# GPS.net
KiCad netlist of a schematic drawn in Altium Designer
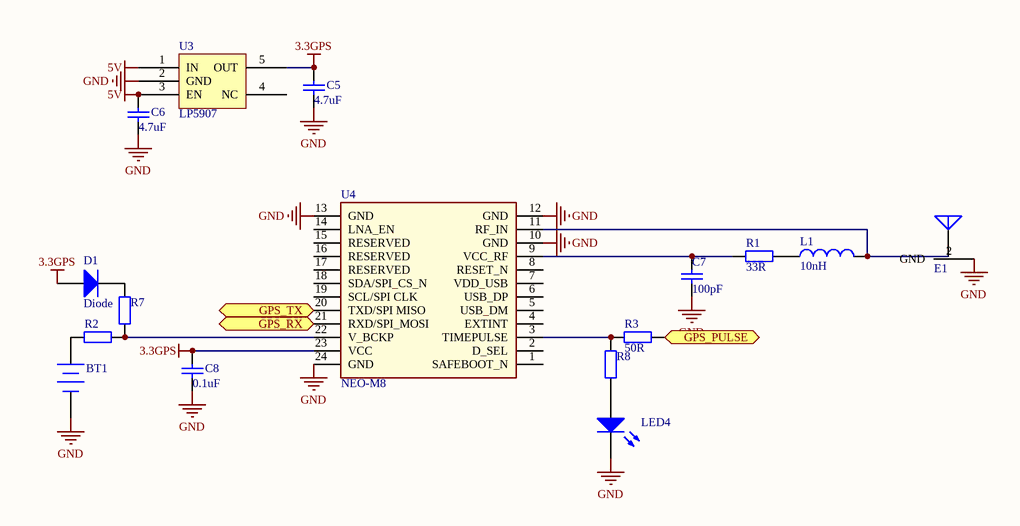
[diagram p0: GPS.SchDoc]

(export (version "E")
  (design (tool "Eeschema 10.0.6"))
  (components
    (comp (ref "BT1")
      (value "Battery")
      (footprint "XH414H-IV01E")
      (description "Multicell Battery")
      (fields (field (name "PUBLISHER") "Altium Limited"))
      (libsource (lib "Miscellaneous Devices") (part "Battery"))
    )
    (comp (ref "C5")
      (value "4.7uF")
      (footprint "0603")
      (description "Capacitor")
      (fields (field (name "PUBLISHER") "Altium Limited"))
      (libsource (lib "RTC6705") (part "Cap"))
    )
    (comp (ref "C6")
      (value "4.7uF")
      (footprint "0603")
      (description "Capacitor")
      (fields (field (name "PUBLISHER") "Altium Limited"))
      (libsource (lib "RTC6705") (part "Cap"))
    )
    (comp (ref "C7")
      (value "100pF")
      (footprint "0402")
      (description "Capacitor")
      (fields (field (name "PUBLISHER") "Altium Limited"))
      (libsource (lib "RTC6705") (part "Cap"))
    )
    (comp (ref "C8")
      (value "0.1uF")
      (footprint "0402")
      (description "Capacitor")
      (fields (field (name "PUBLISHER") "Altium Limited"))
      (libsource (lib "RTC6705") (part "Cap"))
    )
    (comp (ref "D1")
      (value "Diode")
      (footprint "LC-SOD-323")
      (description "Default Diode")
      (fields (field (name "PUBLISHER") "Altium Limited"))
      (libsource (lib "Miscellaneous Devices") (part "Diode"))
    )
    (comp (ref "E1")
      (value "Antenna")
      (footprint "IPEX")
      (description "Generic Antenna")
      (fields (field (name "PUBLISHER") "Altium Limited"))
      (libsource (lib "Miscellaneous Devices") (part "Antenna"))
    )
    (comp (ref "L1")
      (value "10nH")
      (footprint "0402")
      (description "Inductor")
      (fields (field (name "PUBLISHER") "Altium Limited"))
      (libsource (lib "Miscellaneous Devices") (part "Inductor"))
    )
    (comp (ref "LED4")
      (value "LED0")
      (footprint "0603")
      (description "Typical INFRARED GaAs LED")
      (fields (field (name "PUBLISHER") "Altium Limited"))
      (libsource (lib "Miscellaneous Devices") (part "LED0"))
    )
    (comp (ref "R1")
      (value "33R")
      (footprint "0402")
      (description "Resistor")
      (fields (field (name "PUBLISHER") "Altium Limited"))
      (libsource (lib "Miscellaneous Devices") (part "Res2"))
    )
    (comp (ref "R2")
      (value "~")
      (footprint "0402")
      (description "Resistor")
      (fields (field (name "PUBLISHER") "Altium Limited"))
      (libsource (lib "Miscellaneous Devices") (part "Res2"))
    )
    (comp (ref "R3")
      (value "50R")
      (footprint "0402")
      (description "Resistor")
      (fields (field (name "PUBLISHER") "Altium Limited"))
      (libsource (lib "RTC6705") (part "Res2"))
    )
    (comp (ref "R7")
      (value "~")
      (footprint "0402")
      (description "Resistor")
      (fields (field (name "PUBLISHER") "Altium Limited"))
      (libsource (lib "") (part "Res2_1"))
    )
    (comp (ref "R8")
      (value "~")
      (footprint "0402")
      (description "Resistor")
      (fields (field (name "PUBLISHER") "Altium Limited"))
      (libsource (lib "") (part "Res2_1"))
    )
    (comp (ref "U3") (value "LP5907") (footprint "SOT23-5") (libsource (lib "RTC6705") (part "LP5907")))
    (comp (ref "U4")
      (value "NEO-M8")
      (footprint "NEO")
      (description "u-blox NEO GNSS module")
      (fields (field (name "MANUFACTURER") "u-blox"))
      (libsource (lib "ubloxLib") (part "NEO"))
    )
  )
  (nets
    (net (code "1") (name "/GPS_PULSE") (class "Default")
      (node (ref "R3") (pin "1") (pinfunction "1_1") (pintype "passive"))
    )
    (net (code "2") (name "/GPS_RX") (class "Default")
      (node (ref "U4") (pin "21") (pinfunction "RXD/SPI_MOSI_21") (pintype "passive"))
    )
    (net (code "3") (name "/GPS_TX") (class "Default")
      (node (ref "U4") (pin "20") (pinfunction "TXD/SPI_MISO_20") (pintype "passive"))
    )
    (net (code "4") (name "3.3GPS") (class "Default")
      (node (ref "C5") (pin "2") (pinfunction "2_2") (pintype "passive"))
      (node (ref "C8") (pin "2") (pinfunction "2_2") (pintype "passive"))
      (node (ref "D1") (pin "1") (pinfunction "A_1") (pintype "passive"))
      (node (ref "U3") (pin "5") (pinfunction "OUT_5") (pintype "passive"))
      (node (ref "U4") (pin "23") (pinfunction "VCC_23") (pintype "passive"))
    )
    (net (code "5") (name "5V") (class "Default")
      (node (ref "C6") (pin "2") (pinfunction "2_2") (pintype "passive"))
      (node (ref "U3") (pin "1") (pinfunction "IN_1") (pintype "passive"))
      (node (ref "U3") (pin "3") (pinfunction "EN_3") (pintype "passive"))
    )
    (net (code "6") (name "GND") (class "Default")
      (node (ref "BT1") (pin "2") (pinfunction "-_2") (pintype "passive"))
      (node (ref "C5") (pin "1") (pinfunction "1_1") (pintype "passive"))
      (node (ref "C6") (pin "1") (pinfunction "1_1") (pintype "passive"))
      (node (ref "C7") (pin "1") (pinfunction "1_1") (pintype "passive"))
      (node (ref "C8") (pin "1") (pinfunction "1_1") (pintype "passive"))
      (node (ref "E1") (pin "2") (pinfunction "GND_2") (pintype "passive"))
      (node (ref "LED4") (pin "2") (pinfunction "K_2") (pintype "passive"))
      (node (ref "U3") (pin "2") (pinfunction "GND_2") (pintype "passive"))
      (node (ref "U4") (pin "10") (pinfunction "GND_10") (pintype "passive"))
      (node (ref "U4") (pin "12") (pinfunction "GND_12") (pintype "passive"))
      (node (ref "U4") (pin "13") (pinfunction "GND_13") (pintype "passive"))
      (node (ref "U4") (pin "24") (pinfunction "GND_24") (pintype "passive"))
    )
    (net (code "7") (name "Net-(BT1-+)") (class "Default")
      (node (ref "BT1") (pin "1") (pinfunction "+_1") (pintype "passive"))
      (node (ref "R2") (pin "1") (pinfunction "1_1") (pintype "passive"))
    )
    (net (code "8") (name "Net-(D1-K)") (class "Default")
      (node (ref "D1") (pin "2") (pinfunction "K_2") (pintype "passive"))
      (node (ref "R7") (pin "1") (pinfunction "1_1") (pintype "passive"))
    )
    (net (code "9") (name "Net-(E1-ANT)") (class "Default")
      (node (ref "E1") (pin "1") (pinfunction "ANT_1") (pintype "passive"))
      (node (ref "L1") (pin "2") (pinfunction "2_2") (pintype "passive"))
      (node (ref "U4") (pin "11") (pinfunction "RF_IN_11") (pintype "passive"))
    )
    (net (code "10") (name "Net-(L1-Pad1)") (class "Default")
      (node (ref "L1") (pin "1") (pinfunction "1_1") (pintype "passive"))
      (node (ref "R1") (pin "2") (pinfunction "2_2") (pintype "passive"))
    )
    (net (code "11") (name "Net-(LED4-A)") (class "Default")
      (node (ref "LED4") (pin "1") (pinfunction "A_1") (pintype "passive"))
      (node (ref "R8") (pin "2") (pinfunction "2_2") (pintype "passive"))
    )
    (net (code "12") (name "Net-(U4-TIMEPULSE)") (class "Default")
      (node (ref "R3") (pin "2") (pinfunction "2_2") (pintype "passive"))
      (node (ref "R8") (pin "1") (pinfunction "1_1") (pintype "passive"))
      (node (ref "U4") (pin "3") (pinfunction "TIMEPULSE_3") (pintype "passive"))
    )
    (net (code "13") (name "Net-(U4-VCC_RF)") (class "Default")
      (node (ref "C7") (pin "2") (pinfunction "2_2") (pintype "passive"))
      (node (ref "R1") (pin "1") (pinfunction "1_1") (pintype "passive"))
      (node (ref "U4") (pin "9") (pinfunction "VCC_RF_9") (pintype "passive"))
    )
    (net (code "14") (name "Net-(U4-V_BCKP)") (class "Default")
      (node (ref "R2") (pin "2") (pinfunction "2_2") (pintype "passive"))
      (node (ref "R7") (pin "2") (pinfunction "2_2") (pintype "passive"))
      (node (ref "U4") (pin "22") (pinfunction "V_BCKP_22") (pintype "passive"))
    )
    (net (code "15") (name "unconnected-(U3-NC-Pad4)") (class "Default")
      (node (ref "U3") (pin "4") (pinfunction "NC_4") (pintype "passive"))
    )
    (net (code "16") (name "unconnected-(U4-D_SEL-Pad2)") (class "Default")
      (node (ref "U4") (pin "2") (pinfunction "D_SEL_2") (pintype "passive"))
    )
    (net (code "17") (name "unconnected-(U4-EXTINT-Pad4)") (class "Default")
      (node (ref "U4") (pin "4") (pinfunction "EXTINT_4") (pintype "passive"))
    )
    (net (code "18") (name "unconnected-(U4-LNA_EN-Pad14)") (class "Default")
      (node (ref "U4") (pin "14") (pinfunction "LNA_EN_14") (pintype "passive"))
    )
    (net (code "19") (name "unconnected-(U4-RESERVED-Pad15)") (class "Default")
      (node (ref "U4") (pin "15") (pinfunction "RESERVED_15") (pintype "passive"))
    )
    (net (code "20") (name "unconnected-(U4-RESERVED-Pad16)") (class "Default")
      (node (ref "U4") (pin "16") (pinfunction "RESERVED_16") (pintype "passive"))
    )
    (net (code "21") (name "unconnected-(U4-RESERVED-Pad17)") (class "Default")
      (node (ref "U4") (pin "17") (pinfunction "RESERVED_17") (pintype "passive"))
    )
    (net (code "22") (name "unconnected-(U4-RESET_N-Pad8)") (class "Default")
      (node (ref "U4") (pin "8") (pinfunction "RESET_N_8") (pintype "passive"))
    )
    (net (code "23") (name "unconnected-(U4-SAFEBOOT_N-Pad1)") (class "Default")
      (node (ref "U4") (pin "1") (pinfunction "SAFEBOOT_N_1") (pintype "passive"))
    )
    (net (code "24") (name "unconnected-(U4-SCL{slash}SPI_CLK-Pad19)") (class "Default")
      (node (ref "U4") (pin "19") (pinfunction "SCL/SPI_CLK_19") (pintype "passive"))
    )
    (net (code "25") (name "unconnected-(U4-SDA{slash}SPI_CS_N-Pad18)") (class "Default")
      (node (ref "U4") (pin "18") (pinfunction "SDA/SPI_CS_N_18") (pintype "passive"))
    )
    (net (code "26") (name "unconnected-(U4-USB_DM-Pad5)") (class "Default")
      (node (ref "U4") (pin "5") (pinfunction "USB_DM_5") (pintype "passive"))
    )
    (net (code "27") (name "unconnected-(U4-USB_DP-Pad6)") (class "Default")
      (node (ref "U4") (pin "6") (pinfunction "USB_DP_6") (pintype "passive"))
    )
    (net (code "28") (name "unconnected-(U4-VDD_USB-Pad7)") (class "Default")
      (node (ref "U4") (pin "7") (pinfunction "VDD_USB_7") (pintype "passive"))
    )
  )
)
